# WL-FRONT.net
KiCad netlist of a schematic drawn in Altium Designer
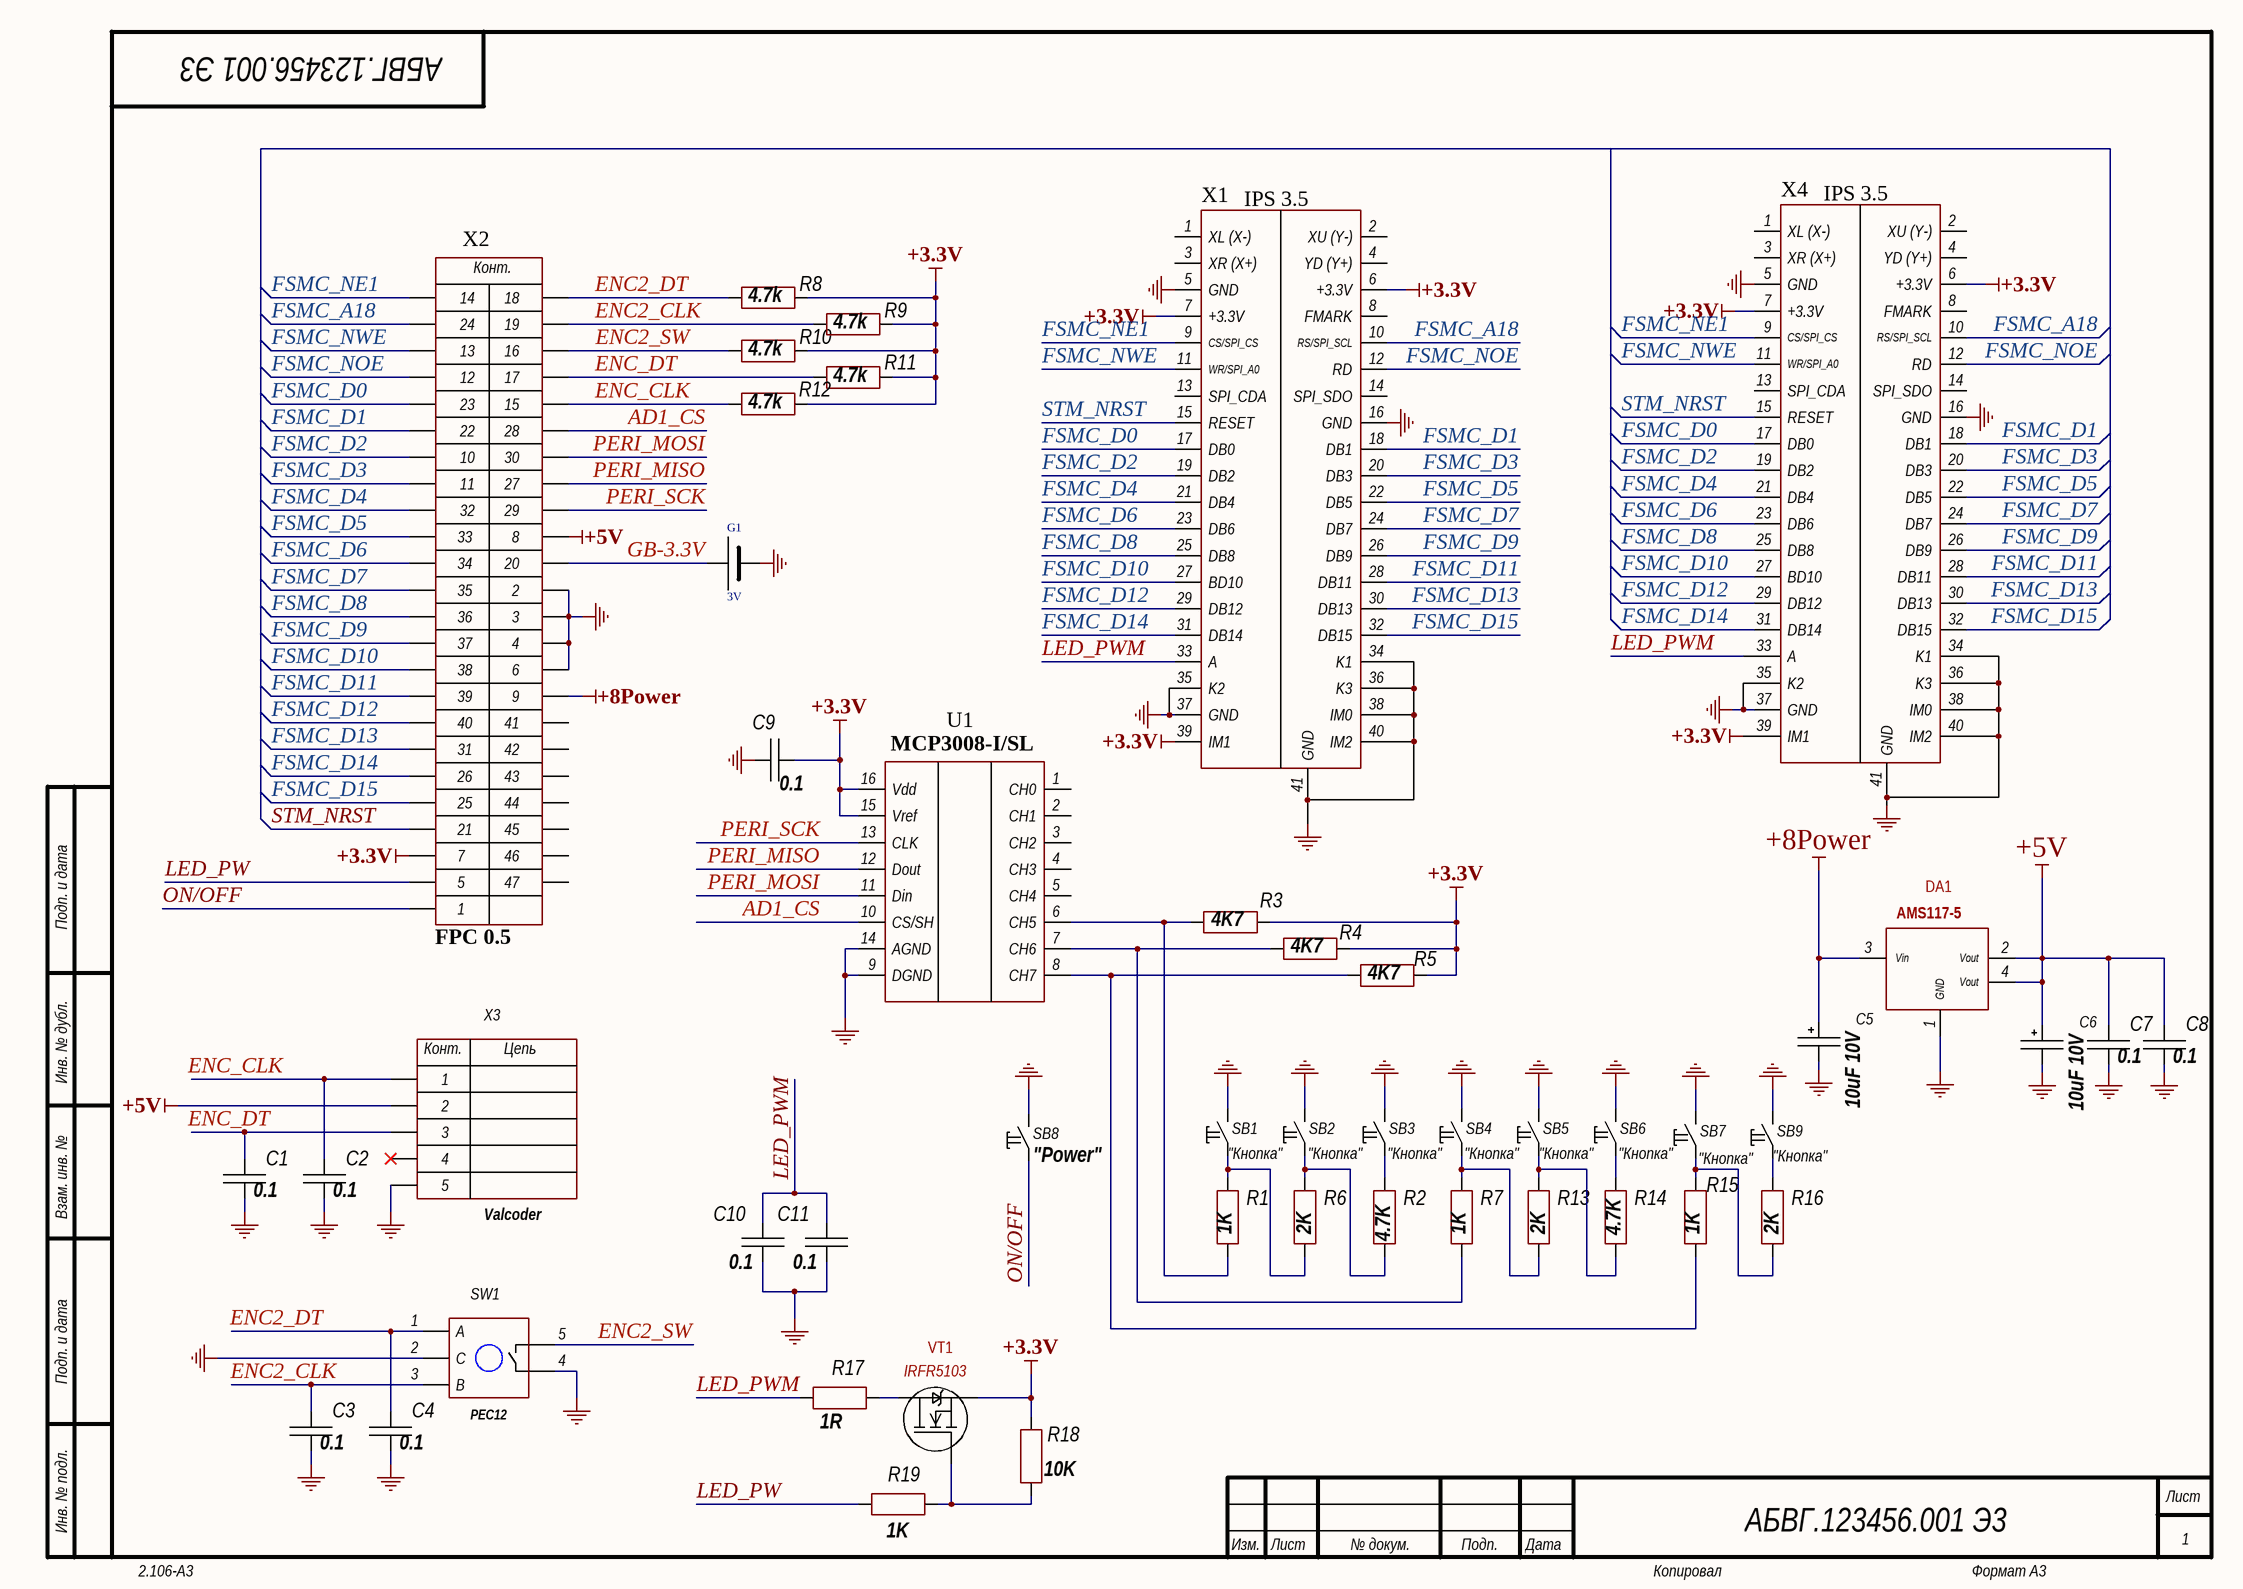
[diagram p0: WL-FRONT.SchDoc]

(export (version "E")
  (design (tool "Eeschema 10.0.6"))
  (components
    (comp (ref "C1")
      (value "0.1")
      (footprint "standard:CH0805C")
      (libsource (lib "Discrete") (part "Capacitor"))
    )
    (comp (ref "C2")
      (value "0.1")
      (footprint "standard:CH0805C")
      (libsource (lib "Discrete") (part "Capacitor"))
    )
    (comp (ref "C3")
      (value "0.1")
      (footprint "standard:CH0805C")
      (libsource (lib "Discrete") (part "Capacitor"))
    )
    (comp (ref "C4")
      (value "0.1")
      (footprint "standard:CH0805C")
      (libsource (lib "Discrete") (part "Capacitor"))
    )
    (comp (ref "C5")
      (value "10uF 10V")
      (footprint "standard:TANTAL_B")
      (libsource (lib "Discrete") (part "TantalCap"))
    )
    (comp (ref "C6")
      (value "10uF 10V")
      (footprint "standard:TANTAL_B")
      (libsource (lib "Discrete") (part "TantalCap"))
    )
    (comp (ref "C7")
      (value "0.1")
      (footprint "standard:CH0805C")
      (libsource (lib "Discrete") (part "Capacitor"))
    )
    (comp (ref "C8")
      (value "0.1")
      (footprint "standard:CH0805C")
      (libsource (lib "Discrete") (part "Capacitor"))
    )
    (comp (ref "C9")
      (value "0.1")
      (footprint "standard:CH0805C")
      (libsource (lib "Discrete") (part "Capacitor"))
    )
    (comp (ref "C10")
      (value "0.1")
      (footprint "standard:CH0805C")
      (libsource (lib "Discrete") (part "Capacitor"))
    )
    (comp (ref "C11")
      (value "0.1")
      (footprint "standard:CH0805C")
      (libsource (lib "Discrete") (part "Capacitor"))
    )
    (comp (ref "DA1") (value "AMS117-5") (footprint "SOT223") (libsource (lib "Analog") (part "AMS117")))
    (comp (ref "G1")
      (value "3V")
      (footprint "BAT: CH224-2032")
      (libsource (lib "Connectors") (part "POWER_BAT"))
    )
    (comp (ref "R1") (value "1K") (footprint "standard:CH0805R") (libsource (lib "") (part "Resistor_1")))
    (comp (ref "R2") (value "4.7K") (footprint "standard:CH0805R") (libsource (lib "") (part "Resistor_1")))
    (comp (ref "R3") (value "4K7") (footprint "standard:CH0805R") (libsource (lib "") (part "Resistor_3")))
    (comp (ref "R4")
      (value "4K7")
      (footprint "standard:CH0805R")
      (libsource (lib "Discrete") (part "Resistor"))
    )
    (comp (ref "R5") (value "4K7") (footprint "standard:CH0805R") (libsource (lib "") (part "Resistor_3")))
    (comp (ref "R6") (value "2K") (footprint "standard:CH0805R") (libsource (lib "") (part "Resistor_1")))
    (comp (ref "R7") (value "1K") (footprint "standard:CH0805R") (libsource (lib "") (part "Resistor_1")))
    (comp (ref "R8") (value "4.7k") (footprint "standard:CH0805R") (libsource (lib "") (part "Resistor_2")))
    (comp (ref "R9") (value "4.7k") (footprint "standard:CH0805R") (libsource (lib "") (part "Resistor_2")))
    (comp (ref "R10") (value "4.7k") (footprint "standard:CH0805R") (libsource (lib "") (part "Resistor_2")))
    (comp (ref "R11") (value "4.7k") (footprint "standard:CH0805R") (libsource (lib "") (part "Resistor_2")))
    (comp (ref "R12") (value "4.7k") (footprint "standard:CH0805R") (libsource (lib "") (part "Resistor_2")))
    (comp (ref "R13") (value "2K") (footprint "standard:CH0805R") (libsource (lib "") (part "Resistor_1")))
    (comp (ref "R14") (value "4.7K") (footprint "standard:CH0805R") (libsource (lib "") (part "Resistor_1")))
    (comp (ref "R15") (value "1K") (footprint "standard:CH0805R") (libsource (lib "") (part "Resistor_1")))
    (comp (ref "R16") (value "2K") (footprint "standard:CH0805R") (libsource (lib "") (part "Resistor_1")))
    (comp (ref "R17") (value "1R") (footprint "standard:CH0805R") (libsource (lib "") (part "Resistor_2")))
    (comp (ref "R18") (value "10K") (footprint "standard:CH0805R") (libsource (lib "") (part "Resistor_1")))
    (comp (ref "R19") (value "1K") (footprint "standard:CH0805R") (libsource (lib "") (part "Resistor_2")))
    (comp (ref "SB1")
      (value "\"Кнопка\"")
      (footprint "BUT: 5X5")
      (description "6x6 mm")
      (libsource (lib "Connectors") (part "Tactile switches"))
    )
    (comp (ref "SB2")
      (value "\"Кнопка\"")
      (footprint "BUT: 5X5")
      (description "6x6 mm")
      (libsource (lib "Connectors") (part "Tactile switches"))
    )
    (comp (ref "SB3")
      (value "\"Кнопка\"")
      (footprint "BUT: 5X5")
      (description "6x6 mm")
      (libsource (lib "Connectors") (part "Tactile switches"))
    )
    (comp (ref "SB4")
      (value "\"Кнопка\"")
      (footprint "BUT: 5X5")
      (description "6x6 mm")
      (libsource (lib "Connectors") (part "Tactile switches"))
    )
    (comp (ref "SB5")
      (value "\"Кнопка\"")
      (footprint "BUT: 5X5")
      (description "6x6 mm")
      (libsource (lib "Connectors") (part "Tactile switches"))
    )
    (comp (ref "SB6")
      (value "\"Кнопка\"")
      (footprint "BUT: 5X5")
      (description "6x6 mm")
      (libsource (lib "Connectors") (part "Tactile switches"))
    )
    (comp (ref "SB7")
      (value "\"Кнопка\"")
      (footprint "BUT: 5X5")
      (description "6x6 mm")
      (libsource (lib "Connectors") (part "Tactile switches"))
    )
    (comp (ref "SB8")
      (value "\"Power\"")
      (footprint "BUT: 5X5")
      (description "6x6 mm")
      (libsource (lib "Connectors") (part "Tactile switches"))
    )
    (comp (ref "SB9")
      (value "\"Кнопка\"")
      (footprint "BUT: 5X5")
      (description "6x6 mm")
      (libsource (lib "Connectors") (part "Tactile switches"))
    )
    (comp (ref "SW1")
      (value "PEC12")
      (footprint "Valkoder-m2")
      (description "Encoder")
      (libsource (lib "Connectors") (part "PEC12"))
    )
    (comp (ref "U1")
      (value "MCP3008-I/SL")
      (footprint "16-SOIC")
      (libsource (lib "Digital") (part "MCP3008-I/SL"))
    )
    (comp (ref "VT1")
      (value "IRFR5103")
      (footprint "SOT23_132")
      (libsource (lib "Transistor") (part "N-KANAL"))
    )
    (comp (ref "X1")
      (value "IPS 3.5")
      (footprint "FPC-40P 0.5mm")
      (libsource (lib "Digital") (part "LCD-IPS 3.5"))
    )
    (comp (ref "X2")
      (value "FPC 0.5")
      (footprint "CON: PBD2x20")
      (libsource (lib "Connectors") (part "FPC-45-0.5"))
    )
    (comp (ref "X3")
      (value "Valcoder")
      (footprint "custom:CON: PLS-5")
      (libsource (lib "Connectors") (part "5-Connector"))
    )
    (comp (ref "X4")
      (value "IPS 3.5")
      (footprint "IPS 3.5 ILI9481")
      (libsource (lib "") (part "LCD-IPS 3.5_1"))
    )
  )
  (nets
    (net (code "1") (name "+3.3V") (class "Default")
      (node (ref "C9") (pin "2") (pinfunction "2_2") (pintype "power_in"))
      (node (ref "R10") (pin "1") (pinfunction "1_1") (pintype "passive"))
      (node (ref "R11") (pin "1") (pinfunction "1_1") (pintype "passive"))
      (node (ref "R12") (pin "1") (pinfunction "1_1") (pintype "passive"))
      (node (ref "R18") (pin "2") (pinfunction "2_2") (pintype "passive"))
      (node (ref "R3") (pin "2") (pinfunction "2_2") (pintype "passive"))
      (node (ref "R4") (pin "2") (pinfunction "2_2") (pintype "passive"))
      (node (ref "R5") (pin "2") (pinfunction "2_2") (pintype "passive"))
      (node (ref "R8") (pin "1") (pinfunction "1_1") (pintype "passive"))
      (node (ref "R9") (pin "1") (pinfunction "1_1") (pintype "passive"))
      (node (ref "U1") (pin "15") (pinfunction "Vref_15") (pintype "passive"))
      (node (ref "U1") (pin "16") (pinfunction "Vdd_16") (pintype "passive"))
      (node (ref "VT1") (pin "2") (pinfunction "I_2") (pintype "passive"))
      (node (ref "X1") (pin "39") (pinfunction "IM1_39") (pintype "passive"))
      (node (ref "X1") (pin "6") (pinfunction "+3.3V_6") (pintype "passive"))
      (node (ref "X1") (pin "7") (pinfunction "+3.3V_7") (pintype "passive"))
      (node (ref "X2") (pin "7") (pinfunction "7_7") (pintype "power_in"))
      (node (ref "X4") (pin "39") (pinfunction "IM1_39") (pintype "passive"))
      (node (ref "X4") (pin "6") (pinfunction "+3.3V_6") (pintype "passive"))
      (node (ref "X4") (pin "7") (pinfunction "+3.3V_7") (pintype "passive"))
    )
    (net (code "2") (name "+5V") (class "Default")
      (node (ref "C6") (pin "1") (pinfunction "1_1") (pintype "power_in"))
      (node (ref "C7") (pin "1") (pinfunction "1_1") (pintype "power_in"))
      (node (ref "C8") (pin "1") (pinfunction "1_1") (pintype "power_in"))
      (node (ref "DA1") (pin "2") (pinfunction "Vout_2") (pintype "passive"))
      (node (ref "DA1") (pin "4") (pinfunction "Vout_4") (pintype "passive"))
      (node (ref "X2") (pin "8") (pinfunction "8_8") (pintype "power_in"))
      (node (ref "X3") (pin "2") (pinfunction "2_2") (pintype "passive"))
    )
    (net (code "3") (name "+8Power") (class "Default")
      (node (ref "C5") (pin "1") (pinfunction "1_1") (pintype "power_in"))
      (node (ref "DA1") (pin "3") (pinfunction "Vin_3") (pintype "passive"))
      (node (ref "X2") (pin "9") (pinfunction "9_9") (pintype "power_in"))
    )
    (net (code "4") (name "/AD1_CS") (class "Default")
      (node (ref "U1") (pin "10") (pinfunction "CS/SH_10") (pintype "passive"))
      (node (ref "X2") (pin "28") (pinfunction "28_28") (pintype "power_in"))
    )
    (net (code "5") (name "/ENC2_CLK") (class "Default")
      (node (ref "C3") (pin "1") (pinfunction "1_1") (pintype "power_in"))
      (node (ref "R9") (pin "2") (pinfunction "2_2") (pintype "passive"))
      (node (ref "SW1") (pin "3") (pinfunction "B_3") (pintype "passive"))
      (node (ref "X2") (pin "19") (pinfunction "19_19") (pintype "power_in"))
    )
    (net (code "6") (name "/ENC2_DT") (class "Default")
      (node (ref "C4") (pin "1") (pinfunction "1_1") (pintype "power_in"))
      (node (ref "R8") (pin "2") (pinfunction "2_2") (pintype "passive"))
      (node (ref "SW1") (pin "1") (pinfunction "A_1") (pintype "passive"))
      (node (ref "X2") (pin "18") (pinfunction "18_18") (pintype "power_in"))
    )
    (net (code "7") (name "/ENC2_SW") (class "Default")
      (node (ref "R10") (pin "2") (pinfunction "2_2") (pintype "passive"))
      (node (ref "SW1") (pin "5") (pinfunction "5_5") (pintype "passive"))
      (node (ref "X2") (pin "16") (pinfunction "16_16") (pintype "power_in"))
    )
    (net (code "8") (name "/ENC_CLK") (class "Default")
      (node (ref "C2") (pin "1") (pinfunction "1_1") (pintype "power_in"))
      (node (ref "R12") (pin "2") (pinfunction "2_2") (pintype "passive"))
      (node (ref "X2") (pin "15") (pinfunction "15_15") (pintype "power_in"))
      (node (ref "X3") (pin "1") (pinfunction "1_1") (pintype "passive"))
    )
    (net (code "9") (name "/ENC_DT") (class "Default")
      (node (ref "C1") (pin "1") (pinfunction "1_1") (pintype "power_in"))
      (node (ref "R11") (pin "2") (pinfunction "2_2") (pintype "passive"))
      (node (ref "X2") (pin "17") (pinfunction "17_17") (pintype "power_in"))
      (node (ref "X3") (pin "3") (pinfunction "3_3") (pintype "power_in"))
    )
    (net (code "10") (name "/FSMC_A18") (class "Default")
      (node (ref "X1") (pin "10") (pinfunction "RS/SPI_SCL_10") (pintype "passive"))
      (node (ref "X2") (pin "24") (pinfunction "24_24") (pintype "passive"))
      (node (ref "X4") (pin "10") (pinfunction "RS/SPI_SCL_10") (pintype "passive"))
    )
    (net (code "11") (name "/FSMC_D0") (class "Default")
      (node (ref "X1") (pin "17") (pinfunction "DB0_17") (pintype "passive"))
      (node (ref "X2") (pin "23") (pinfunction "23_23") (pintype "power_in"))
      (node (ref "X4") (pin "17") (pinfunction "DB0_17") (pintype "passive"))
    )
    (net (code "12") (name "/FSMC_D1") (class "Default")
      (node (ref "X1") (pin "18") (pinfunction "DB1_18") (pintype "passive"))
      (node (ref "X2") (pin "22") (pinfunction "22_22") (pintype "power_in"))
      (node (ref "X4") (pin "18") (pinfunction "DB1_18") (pintype "passive"))
    )
    (net (code "13") (name "/FSMC_D2") (class "Default")
      (node (ref "X1") (pin "19") (pinfunction "DB2_19") (pintype "passive"))
      (node (ref "X2") (pin "10") (pinfunction "10_10") (pintype "power_in"))
      (node (ref "X4") (pin "19") (pinfunction "DB2_19") (pintype "passive"))
    )
    (net (code "14") (name "/FSMC_D3") (class "Default")
      (node (ref "X1") (pin "20") (pinfunction "DB3_20") (pintype "passive"))
      (node (ref "X2") (pin "11") (pinfunction "11_11") (pintype "power_in"))
      (node (ref "X4") (pin "20") (pinfunction "DB3_20") (pintype "passive"))
    )
    (net (code "15") (name "/FSMC_D4") (class "Default")
      (node (ref "X1") (pin "21") (pinfunction "DB4_21") (pintype "passive"))
      (node (ref "X2") (pin "32") (pinfunction "32_32") (pintype "power_in"))
      (node (ref "X4") (pin "21") (pinfunction "DB4_21") (pintype "passive"))
    )
    (net (code "16") (name "/FSMC_D5") (class "Default")
      (node (ref "X1") (pin "22") (pinfunction "DB5_22") (pintype "passive"))
      (node (ref "X2") (pin "33") (pinfunction "33_33") (pintype "power_in"))
      (node (ref "X4") (pin "22") (pinfunction "DB5_22") (pintype "passive"))
    )
    (net (code "17") (name "/FSMC_D6") (class "Default")
      (node (ref "X1") (pin "23") (pinfunction "DB6_23") (pintype "passive"))
      (node (ref "X2") (pin "34") (pinfunction "34_34") (pintype "power_in"))
      (node (ref "X4") (pin "23") (pinfunction "DB6_23") (pintype "passive"))
    )
    (net (code "18") (name "/FSMC_D7") (class "Default")
      (node (ref "X1") (pin "24") (pinfunction "DB7_24") (pintype "passive"))
      (node (ref "X2") (pin "35") (pinfunction "35_35") (pintype "power_in"))
      (node (ref "X4") (pin "24") (pinfunction "DB7_24") (pintype "passive"))
    )
    (net (code "19") (name "/FSMC_D8") (class "Default")
      (node (ref "X1") (pin "25") (pinfunction "DB8_25") (pintype "passive"))
      (node (ref "X2") (pin "36") (pinfunction "36_36") (pintype "power_in"))
      (node (ref "X4") (pin "25") (pinfunction "DB8_25") (pintype "passive"))
    )
    (net (code "20") (name "/FSMC_D9") (class "Default")
      (node (ref "X1") (pin "26") (pinfunction "DB9_26") (pintype "passive"))
      (node (ref "X2") (pin "37") (pinfunction "37_37") (pintype "power_in"))
      (node (ref "X4") (pin "26") (pinfunction "DB9_26") (pintype "passive"))
    )
    (net (code "21") (name "/FSMC_D10") (class "Default")
      (node (ref "X1") (pin "27") (pinfunction "BD10_27") (pintype "passive"))
      (node (ref "X2") (pin "38") (pinfunction "38_38") (pintype "power_in"))
      (node (ref "X4") (pin "27") (pinfunction "BD10_27") (pintype "passive"))
    )
    (net (code "22") (name "/FSMC_D11") (class "Default")
      (node (ref "X1") (pin "28") (pinfunction "DB11_28") (pintype "passive"))
      (node (ref "X2") (pin "39") (pinfunction "39_39") (pintype "power_in"))
      (node (ref "X4") (pin "28") (pinfunction "DB11_28") (pintype "passive"))
    )
    (net (code "23") (name "/FSMC_D12") (class "Default")
      (node (ref "X1") (pin "29") (pinfunction "DB12_29") (pintype "passive"))
      (node (ref "X2") (pin "40") (pinfunction "40_40") (pintype "power_in"))
      (node (ref "X4") (pin "29") (pinfunction "DB12_29") (pintype "passive"))
    )
    (net (code "24") (name "/FSMC_D13") (class "Default")
      (node (ref "X1") (pin "30") (pinfunction "DB13_30") (pintype "passive"))
      (node (ref "X2") (pin "31") (pinfunction "31_31") (pintype "power_in"))
      (node (ref "X4") (pin "30") (pinfunction "DB13_30") (pintype "passive"))
    )
    (net (code "25") (name "/FSMC_D14") (class "Default")
      (node (ref "X1") (pin "31") (pinfunction "DB14_31") (pintype "passive"))
      (node (ref "X2") (pin "26") (pinfunction "26_26") (pintype "power_in"))
      (node (ref "X4") (pin "31") (pinfunction "DB14_31") (pintype "passive"))
    )
    (net (code "26") (name "/FSMC_D15") (class "Default")
      (node (ref "X1") (pin "32") (pinfunction "DB15_32") (pintype "passive"))
      (node (ref "X2") (pin "25") (pinfunction "25_25") (pintype "power_in"))
      (node (ref "X4") (pin "32") (pinfunction "DB15_32") (pintype "passive"))
    )
    (net (code "27") (name "/FSMC_NE1") (class "Default")
      (node (ref "X1") (pin "9") (pinfunction "CS/SPI_CS_9") (pintype "passive"))
      (node (ref "X2") (pin "14") (pinfunction "14_14") (pintype "passive"))
      (node (ref "X4") (pin "9") (pinfunction "CS/SPI_CS_9") (pintype "passive"))
    )
    (net (code "28") (name "/FSMC_NOE") (class "Default")
      (node (ref "X1") (pin "12") (pinfunction "RD_12") (pintype "passive"))
      (node (ref "X2") (pin "12") (pinfunction "12_12") (pintype "power_in"))
      (node (ref "X4") (pin "12") (pinfunction "RD_12") (pintype "passive"))
    )
    (net (code "29") (name "/FSMC_NWE") (class "Default")
      (node (ref "X1") (pin "11") (pinfunction "WR/SPI_A0_11") (pintype "passive"))
      (node (ref "X2") (pin "13") (pinfunction "13_13") (pintype "power_in"))
      (node (ref "X4") (pin "11") (pinfunction "WR/SPI_A0_11") (pintype "passive"))
    )
    (net (code "30") (name "/GB-3.3V") (class "Default")
      (node (ref "G1") (pin "1") (pinfunction "0_1") (pintype "passive"))
      (node (ref "X2") (pin "20") (pinfunction "20_20") (pintype "power_in"))
    )
    (net (code "31") (name "/LED_PW") (class "Default")
      (node (ref "R19") (pin "2") (pinfunction "2_2") (pintype "passive"))
      (node (ref "X2") (pin "5") (pinfunction "5_5") (pintype "power_in"))
    )
    (net (code "32") (name "/LED_PWM") (class "Default")
      (node (ref "C10") (pin "1") (pinfunction "1_1") (pintype "power_in"))
      (node (ref "C11") (pin "1") (pinfunction "1_1") (pintype "power_in"))
      (node (ref "R17") (pin "2") (pinfunction "2_2") (pintype "passive"))
      (node (ref "X1") (pin "33") (pinfunction "A_33") (pintype "passive"))
      (node (ref "X4") (pin "33") (pinfunction "A_33") (pintype "passive"))
    )
    (net (code "33") (name "/ON{slash}OFF") (class "Default")
      (node (ref "SB8") (pin "1") (pinfunction "1_1") (pintype "passive"))
      (node (ref "X2") (pin "1") (pinfunction "1_1") (pintype "power_in"))
    )
    (net (code "34") (name "/PERI_MISO") (class "Default")
      (node (ref "U1") (pin "12") (pinfunction "Dout_12") (pintype "passive"))
      (node (ref "X2") (pin "27") (pinfunction "27_27") (pintype "power_in"))
    )
    (net (code "35") (name "/PERI_MOSI") (class "Default")
      (node (ref "U1") (pin "11") (pinfunction "Din_11") (pintype "passive"))
      (node (ref "X2") (pin "30") (pinfunction "30_30") (pintype "power_in"))
    )
    (net (code "36") (name "/PERI_SCK") (class "Default")
      (node (ref "U1") (pin "13") (pinfunction "CLK_13") (pintype "passive"))
      (node (ref "X2") (pin "29") (pinfunction "29_29") (pintype "power_in"))
    )
    (net (code "37") (name "/STM_NRST") (class "Default")
      (node (ref "X1") (pin "15") (pinfunction "RESET_15") (pintype "passive"))
      (node (ref "X2") (pin "21") (pinfunction "21_21") (pintype "power_in"))
      (node (ref "X4") (pin "15") (pinfunction "RESET_15") (pintype "passive"))
    )
    (net (code "38") (name "GND") (class "Default")
      (node (ref "C1") (pin "2") (pinfunction "2_2") (pintype "power_in"))
      (node (ref "C10") (pin "2") (pinfunction "2_2") (pintype "power_in"))
      (node (ref "C11") (pin "2") (pinfunction "2_2") (pintype "power_in"))
      (node (ref "C2") (pin "2") (pinfunction "2_2") (pintype "power_in"))
      (node (ref "C3") (pin "2") (pinfunction "2_2") (pintype "power_in"))
      (node (ref "C4") (pin "2") (pinfunction "2_2") (pintype "power_in"))
      (node (ref "C5") (pin "2") (pinfunction "2_2") (pintype "power_in"))
      (node (ref "C6") (pin "2") (pinfunction "2_2") (pintype "power_in"))
      (node (ref "C7") (pin "2") (pinfunction "2_2") (pintype "power_in"))
      (node (ref "C8") (pin "2") (pinfunction "2_2") (pintype "power_in"))
      (node (ref "C9") (pin "1") (pinfunction "1_1") (pintype "power_in"))
      (node (ref "DA1") (pin "1") (pinfunction "GND_1") (pintype "passive"))
      (node (ref "G1") (pin "2") (pinfunction "1_2") (pintype "passive"))
      (node (ref "SB1") (pin "2") (pinfunction "2_2") (pintype "passive"))
      (node (ref "SB2") (pin "2") (pinfunction "2_2") (pintype "passive"))
      (node (ref "SB3") (pin "2") (pinfunction "2_2") (pintype "passive"))
      (node (ref "SB4") (pin "2") (pinfunction "2_2") (pintype "passive"))
      (node (ref "SB5") (pin "2") (pinfunction "2_2") (pintype "passive"))
      (node (ref "SB6") (pin "2") (pinfunction "2_2") (pintype "passive"))
      (node (ref "SB7") (pin "2") (pinfunction "2_2") (pintype "passive"))
      (node (ref "SB8") (pin "2") (pinfunction "2_2") (pintype "passive"))
      (node (ref "SB9") (pin "2") (pinfunction "2_2") (pintype "passive"))
      (node (ref "SW1") (pin "2") (pinfunction "C_2") (pintype "passive"))
      (node (ref "SW1") (pin "4") (pinfunction "4_4") (pintype "passive"))
      (node (ref "U1") (pin "14") (pinfunction "AGND_14") (pintype "passive"))
      (node (ref "U1") (pin "9") (pinfunction "DGND_9") (pintype "passive"))
      (node (ref "X1") (pin "16") (pinfunction "GND_16") (pintype "passive"))
      (node (ref "X1") (pin "34") (pinfunction "K1_34") (pintype "passive"))
      (node (ref "X1") (pin "35") (pinfunction "K2_35") (pintype "passive"))
      (node (ref "X1") (pin "36") (pinfunction "K3_36") (pintype "passive"))
      (node (ref "X1") (pin "37") (pinfunction "GND_37") (pintype "passive"))
      (node (ref "X1") (pin "38") (pinfunction "IM0_38") (pintype "passive"))
      (node (ref "X1") (pin "40") (pinfunction "IM2_40") (pintype "passive"))
      (node (ref "X1") (pin "41") (pinfunction "GND_41") (pintype "passive"))
      (node (ref "X1") (pin "5") (pinfunction "GND_5") (pintype "passive"))
      (node (ref "X2") (pin "2") (pinfunction "2_2") (pintype "power_in"))
      (node (ref "X2") (pin "3") (pinfunction "3_3") (pintype "power_in"))
      (node (ref "X2") (pin "4") (pinfunction "4_4") (pintype "power_in"))
      (node (ref "X2") (pin "6") (pinfunction "6_6") (pintype "power_in"))
      (node (ref "X3") (pin "5") (pinfunction "5_5") (pintype "power_in"))
      (node (ref "X4") (pin "16") (pinfunction "GND_16") (pintype "passive"))
      (node (ref "X4") (pin "34") (pinfunction "K1_34") (pintype "passive"))
      (node (ref "X4") (pin "35") (pinfunction "K2_35") (pintype "passive"))
      (node (ref "X4") (pin "36") (pinfunction "K3_36") (pintype "passive"))
      (node (ref "X4") (pin "37") (pinfunction "GND_37") (pintype "passive"))
      (node (ref "X4") (pin "38") (pinfunction "IM0_38") (pintype "passive"))
      (node (ref "X4") (pin "40") (pinfunction "IM2_40") (pintype "passive"))
      (node (ref "X4") (pin "41") (pinfunction "GND_41") (pintype "passive"))
      (node (ref "X4") (pin "5") (pinfunction "GND_5") (pintype "passive"))
    )
    (net (code "39") (name "Net-(R1-Pad2)") (class "Default")
      (node (ref "R1") (pin "2") (pinfunction "2_2") (pintype "passive"))
      (node (ref "R6") (pin "1") (pinfunction "1_1") (pintype "passive"))
      (node (ref "SB1") (pin "1") (pinfunction "1_1") (pintype "passive"))
    )
    (net (code "40") (name "Net-(R2-Pad1)") (class "Default")
      (node (ref "R2") (pin "1") (pinfunction "1_1") (pintype "passive"))
      (node (ref "R6") (pin "2") (pinfunction "2_2") (pintype "passive"))
      (node (ref "SB2") (pin "1") (pinfunction "1_1") (pintype "passive"))
    )
    (net (code "41") (name "Net-(R2-Pad2)") (class "Default")
      (node (ref "R2") (pin "2") (pinfunction "2_2") (pintype "passive"))
      (node (ref "SB3") (pin "1") (pinfunction "1_1") (pintype "passive"))
    )
    (net (code "42") (name "Net-(R13-Pad1)") (class "Default")
      (node (ref "R13") (pin "1") (pinfunction "1_1") (pintype "passive"))
      (node (ref "R7") (pin "2") (pinfunction "2_2") (pintype "passive"))
      (node (ref "SB4") (pin "1") (pinfunction "1_1") (pintype "passive"))
    )
    (net (code "43") (name "Net-(R13-Pad2)") (class "Default")
      (node (ref "R13") (pin "2") (pinfunction "2_2") (pintype "passive"))
      (node (ref "R14") (pin "1") (pinfunction "1_1") (pintype "passive"))
      (node (ref "SB5") (pin "1") (pinfunction "1_1") (pintype "passive"))
    )
    (net (code "44") (name "Net-(R14-Pad2)") (class "Default")
      (node (ref "R14") (pin "2") (pinfunction "2_2") (pintype "passive"))
      (node (ref "SB6") (pin "1") (pinfunction "1_1") (pintype "passive"))
    )
    (net (code "45") (name "Net-(R15-Pad2)") (class "Default")
      (node (ref "R15") (pin "2") (pinfunction "2_2") (pintype "passive"))
      (node (ref "R16") (pin "1") (pinfunction "1_1") (pintype "passive"))
      (node (ref "SB7") (pin "1") (pinfunction "1_1") (pintype "passive"))
    )
    (net (code "46") (name "Net-(R16-Pad2)") (class "Default")
      (node (ref "R16") (pin "2") (pinfunction "2_2") (pintype "passive"))
      (node (ref "SB9") (pin "1") (pinfunction "1_1") (pintype "passive"))
    )
    (net (code "47") (name "Net-(U1-CH5)") (class "Default")
      (node (ref "R1") (pin "1") (pinfunction "1_1") (pintype "passive"))
      (node (ref "R3") (pin "1") (pinfunction "1_1") (pintype "passive"))
      (node (ref "U1") (pin "6") (pinfunction "CH5_6") (pintype "passive"))
    )
    (net (code "48") (name "Net-(U1-CH6)") (class "Default")
      (node (ref "R4") (pin "1") (pinfunction "1_1") (pintype "passive"))
      (node (ref "R7") (pin "1") (pinfunction "1_1") (pintype "passive"))
      (node (ref "U1") (pin "7") (pinfunction "CH6_7") (pintype "passive"))
    )
    (net (code "49") (name "Net-(U1-CH7)") (class "Default")
      (node (ref "R15") (pin "1") (pinfunction "1_1") (pintype "passive"))
      (node (ref "R5") (pin "1") (pinfunction "1_1") (pintype "passive"))
      (node (ref "U1") (pin "8") (pinfunction "CH7_8") (pintype "passive"))
    )
    (net (code "50") (name "Net-(VT1-Затвор(Gate))") (class "Default")
      (node (ref "R18") (pin "1") (pinfunction "1_1") (pintype "passive"))
      (node (ref "R19") (pin "1") (pinfunction "1_1") (pintype "passive"))
      (node (ref "VT1") (pin "1") (pinfunction "Затвор(Gate)_1") (pintype "passive"))
    )
    (net (code "51") (name "Net-(VT1-Сток(Drain))") (class "Default")
      (node (ref "R17") (pin "1") (pinfunction "1_1") (pintype "passive"))
      (node (ref "VT1") (pin "3") (pinfunction "Сток(Drain)_3") (pintype "passive"))
    )
    (net (code "52") (name "unconnected-(U1-CH0-Pad1)") (class "Default")
      (node (ref "U1") (pin "1") (pinfunction "CH0_1") (pintype "passive"))
    )
    (net (code "53") (name "unconnected-(U1-CH1-Pad2)") (class "Default")
      (node (ref "U1") (pin "2") (pinfunction "CH1_2") (pintype "passive"))
    )
    (net (code "54") (name "unconnected-(U1-CH2-Pad3)") (class "Default")
      (node (ref "U1") (pin "3") (pinfunction "CH2_3") (pintype "passive"))
    )
    (net (code "55") (name "unconnected-(U1-CH3-Pad4)") (class "Default")
      (node (ref "U1") (pin "4") (pinfunction "CH3_4") (pintype "passive"))
    )
    (net (code "56") (name "unconnected-(U1-CH4-Pad5)") (class "Default")
      (node (ref "U1") (pin "5") (pinfunction "CH4_5") (pintype "passive"))
    )
    (net (code "57") (name "unconnected-(X1-FMARK-Pad8)") (class "Default")
      (node (ref "X1") (pin "8") (pinfunction "FMARK_8") (pintype "passive"))
    )
    (net (code "58") (name "unconnected-(X1-SPI_CDA-Pad13)") (class "Default")
      (node (ref "X1") (pin "13") (pinfunction "SPI_CDA_13") (pintype "passive"))
    )
    (net (code "59") (name "unconnected-(X1-SPI_SDO-Pad14)") (class "Default")
      (node (ref "X1") (pin "14") (pinfunction "SPI_SDO_14") (pintype "passive"))
    )
    (net (code "60") (name "unconnected-(X1-XL_(X-)-Pad1)") (class "Default")
      (node (ref "X1") (pin "1") (pinfunction "XL_(X-)_1") (pintype "passive"))
    )
    (net (code "61") (name "unconnected-(X1-XR_(X+)-Pad3)") (class "Default")
      (node (ref "X1") (pin "3") (pinfunction "XR_(X+)_3") (pintype "passive"))
    )
    (net (code "62") (name "unconnected-(X1-XU_(Y-)-Pad2)") (class "Default")
      (node (ref "X1") (pin "2") (pinfunction "XU_(Y-)_2") (pintype "passive"))
    )
    (net (code "63") (name "unconnected-(X1-YD_(Y+)-Pad4)") (class "Default")
      (node (ref "X1") (pin "4") (pinfunction "YD_(Y+)_4") (pintype "passive"))
    )
    (net (code "64") (name "unconnected-(X2-Pad41)") (class "Default")
      (node (ref "X2") (pin "41") (pinfunction "41_41") (pintype "power_in"))
    )
    (net (code "65") (name "unconnected-(X2-Pad42)") (class "Default")
      (node (ref "X2") (pin "42") (pinfunction "42_42") (pintype "power_in"))
    )
    (net (code "66") (name "unconnected-(X2-Pad43)") (class "Default")
      (node (ref "X2") (pin "43") (pinfunction "43_43") (pintype "power_in"))
    )
    (net (code "67") (name "unconnected-(X2-Pad44)") (class "Default")
      (node (ref "X2") (pin "44") (pinfunction "44_44") (pintype "power_in"))
    )
    (net (code "68") (name "unconnected-(X2-Pad45)") (class "Default")
      (node (ref "X2") (pin "45") (pinfunction "45_45") (pintype "power_in"))
    )
    (net (code "69") (name "unconnected-(X2-Pad46)") (class "Default")
      (node (ref "X2") (pin "46") (pinfunction "46_46") (pintype "power_in"))
    )
    (net (code "70") (name "unconnected-(X2-Pad47)") (class "Default")
      (node (ref "X2") (pin "47") (pinfunction "47_47") (pintype "power_in"))
    )
    (net (code "71") (name "unconnected-(X3-Pad4)") (class "Default")
      (node (ref "X3") (pin "4") (pinfunction "4_4") (pintype "power_in+no_connect"))
    )
    (net (code "72") (name "unconnected-(X4-FMARK-Pad8)") (class "Default")
      (node (ref "X4") (pin "8") (pinfunction "FMARK_8") (pintype "passive"))
    )
    (net (code "73") (name "unconnected-(X4-SPI_CDA-Pad13)") (class "Default")
      (node (ref "X4") (pin "13") (pinfunction "SPI_CDA_13") (pintype "passive"))
    )
    (net (code "74") (name "unconnected-(X4-SPI_SDO-Pad14)") (class "Default")
      (node (ref "X4") (pin "14") (pinfunction "SPI_SDO_14") (pintype "passive"))
    )
    (net (code "75") (name "unconnected-(X4-XL_(X-)-Pad1)") (class "Default")
      (node (ref "X4") (pin "1") (pinfunction "XL_(X-)_1") (pintype "passive"))
    )
    (net (code "76") (name "unconnected-(X4-XR_(X+)-Pad3)") (class "Default")
      (node (ref "X4") (pin "3") (pinfunction "XR_(X+)_3") (pintype "passive"))
    )
    (net (code "77") (name "unconnected-(X4-XU_(Y-)-Pad2)") (class "Default")
      (node (ref "X4") (pin "2") (pinfunction "XU_(Y-)_2") (pintype "passive"))
    )
    (net (code "78") (name "unconnected-(X4-YD_(Y+)-Pad4)") (class "Default")
      (node (ref "X4") (pin "4") (pinfunction "YD_(Y+)_4") (pintype "passive"))
    )
  )
)
